# digital-ps.net
KiCad netlist of a schematic drawn in EAGLE
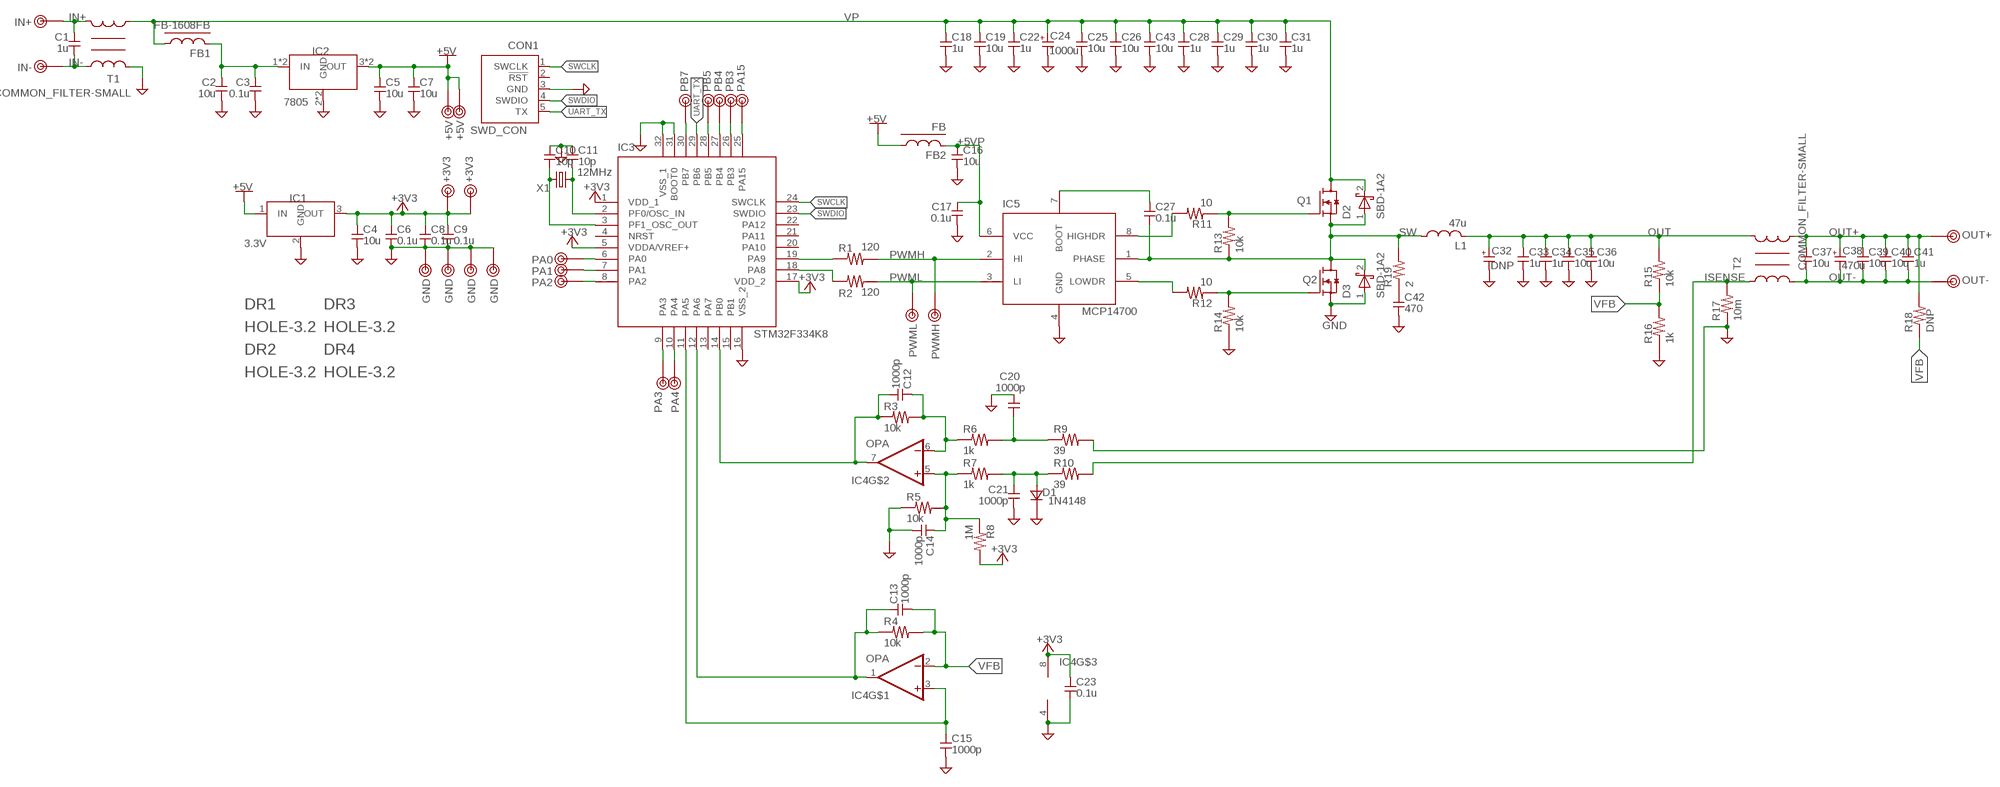
[diagram p0: schematic, sheet 1]

(export (version "E")
  (design (tool "Eeschema 10.0.6"))
  (components
    (comp (ref "C1")
      (value "1u")
      (footprint "eagle-import:2012-2")
      (libsource (lib "eagle-import") (part "C-2012-2"))
    )
    (comp (ref "C2")
      (value "10u")
      (footprint "eagle-import:3216")
      (libsource (lib "eagle-import") (part "C-3216"))
    )
    (comp (ref "C3")
      (value "0.1u")
      (footprint "eagle-import:1608")
      (libsource (lib "eagle-import") (part "C-1608"))
    )
    (comp (ref "C4")
      (value "10u")
      (footprint "eagle-import:2012")
      (libsource (lib "eagle-import") (part "C-2012"))
    )
    (comp (ref "C5")
      (value "10u")
      (footprint "eagle-import:2012")
      (libsource (lib "eagle-import") (part "C-2012"))
    )
    (comp (ref "C6")
      (value "0.1u")
      (footprint "eagle-import:1608")
      (libsource (lib "eagle-import") (part "C-1608"))
    )
    (comp (ref "C7")
      (value "10u")
      (footprint "eagle-import:2012")
      (libsource (lib "eagle-import") (part "C-2012"))
    )
    (comp (ref "C8")
      (value "0.1u")
      (footprint "eagle-import:1608")
      (libsource (lib "eagle-import") (part "C-1608"))
    )
    (comp (ref "C9")
      (value "0.1u")
      (footprint "eagle-import:1608")
      (libsource (lib "eagle-import") (part "C-1608"))
    )
    (comp (ref "C10")
      (value "10p")
      (footprint "eagle-import:1608")
      (libsource (lib "eagle-import") (part "C-1608"))
    )
    (comp (ref "C11")
      (value "10p")
      (footprint "eagle-import:1608")
      (libsource (lib "eagle-import") (part "C-1608"))
    )
    (comp (ref "C12")
      (value "1000p")
      (footprint "eagle-import:1608")
      (libsource (lib "eagle-import") (part "C-1608"))
    )
    (comp (ref "C13")
      (value "1000p")
      (footprint "eagle-import:1608")
      (libsource (lib "eagle-import") (part "C-1608"))
    )
    (comp (ref "C14")
      (value "1000p")
      (footprint "eagle-import:1608")
      (libsource (lib "eagle-import") (part "C-1608"))
    )
    (comp (ref "C15")
      (value "1000p")
      (footprint "eagle-import:1608")
      (libsource (lib "eagle-import") (part "C-1608"))
    )
    (comp (ref "C16")
      (value "10u")
      (footprint "eagle-import:2012")
      (libsource (lib "eagle-import") (part "C-2012"))
    )
    (comp (ref "C17")
      (value "0.1u")
      (footprint "eagle-import:1608")
      (libsource (lib "eagle-import") (part "C-1608"))
    )
    (comp (ref "C18")
      (value "1u")
      (footprint "eagle-import:1608-2")
      (libsource (lib "eagle-import") (part "C-1608-2"))
    )
    (comp (ref "C19")
      (value "10u")
      (footprint "eagle-import:3225-2")
      (libsource (lib "eagle-import") (part "C-3225-2"))
    )
    (comp (ref "C20")
      (value "1000p")
      (footprint "eagle-import:1608")
      (libsource (lib "eagle-import") (part "C-1608"))
    )
    (comp (ref "C21")
      (value "1000p")
      (footprint "eagle-import:1608")
      (libsource (lib "eagle-import") (part "C-1608"))
    )
    (comp (ref "C22")
      (value "1u")
      (footprint "eagle-import:1608-2")
      (libsource (lib "eagle-import") (part "C-1608-2"))
    )
    (comp (ref "C23")
      (value "0.1u")
      (footprint "eagle-import:1608")
      (libsource (lib "eagle-import") (part "C-1608"))
    )
    (comp (ref "C24")
      (value "1000u")
      (footprint "eagle-import:E5-13")
      (libsource (lib "eagle-import") (part "CPOLE5-13"))
    )
    (comp (ref "C25")
      (value "10u")
      (footprint "eagle-import:3225-2")
      (libsource (lib "eagle-import") (part "C-3225-2"))
    )
    (comp (ref "C26")
      (value "10u")
      (footprint "eagle-import:3225-2")
      (libsource (lib "eagle-import") (part "C-3225-2"))
    )
    (comp (ref "C27")
      (value "0.1u")
      (footprint "eagle-import:1608")
      (libsource (lib "eagle-import") (part "C-1608"))
    )
    (comp (ref "C28")
      (value "1u")
      (footprint "eagle-import:1608-2")
      (libsource (lib "eagle-import") (part "C-1608-2"))
    )
    (comp (ref "C29")
      (value "1u")
      (footprint "eagle-import:1608-2")
      (libsource (lib "eagle-import") (part "C-1608-2"))
    )
    (comp (ref "C30")
      (value "1u")
      (footprint "eagle-import:1608-2")
      (libsource (lib "eagle-import") (part "C-1608-2"))
    )
    (comp (ref "C31")
      (value "1u")
      (footprint "eagle-import:1608-2")
      (libsource (lib "eagle-import") (part "C-1608-2"))
    )
    (comp (ref "C32")
      (value "DNP")
      (footprint "eagle-import:E5-13")
      (libsource (lib "eagle-import") (part "CPOLE5-13"))
    )
    (comp (ref "C33")
      (value "1u")
      (footprint "eagle-import:1608-2")
      (libsource (lib "eagle-import") (part "C-1608-2"))
    )
    (comp (ref "C34")
      (value "1u")
      (footprint "eagle-import:1608-2")
      (libsource (lib "eagle-import") (part "C-1608-2"))
    )
    (comp (ref "C35")
      (value "10u")
      (footprint "eagle-import:3225-2")
      (libsource (lib "eagle-import") (part "C-3225-2"))
    )
    (comp (ref "C36")
      (value "10u")
      (footprint "eagle-import:3225-2")
      (libsource (lib "eagle-import") (part "C-3225-2"))
    )
    (comp (ref "C37")
      (value "10u")
      (footprint "eagle-import:3225-2")
      (libsource (lib "eagle-import") (part "C-3225-2"))
    )
    (comp (ref "C38")
      (value "470u")
      (footprint "eagle-import:E5-13")
      (libsource (lib "eagle-import") (part "CPOLE5-13"))
    )
    (comp (ref "C39")
      (value "10u")
      (footprint "eagle-import:3225-2")
      (libsource (lib "eagle-import") (part "C-3225-2"))
    )
    (comp (ref "C40")
      (value "10u")
      (footprint "eagle-import:3225-2")
      (libsource (lib "eagle-import") (part "C-3225-2"))
    )
    (comp (ref "C41")
      (value "1u")
      (footprint "eagle-import:1608-2")
      (libsource (lib "eagle-import") (part "C-1608-2"))
    )
    (comp (ref "C42")
      (value "470")
      (footprint "eagle-import:1608-2")
      (libsource (lib "eagle-import") (part "C-1608-2"))
    )
    (comp (ref "C43")
      (value "10u")
      (footprint "eagle-import:3225-2")
      (libsource (lib "eagle-import") (part "C-3225-2"))
    )
    (comp (ref "CON1")
      (value "SWD_CON")
      (footprint "eagle-import:SWD_CON")
      (libsource (lib "eagle-import") (part "SWD_CON"))
    )
    (comp (ref "D1")
      (value "1N4148")
      (footprint "eagle-import:SOD123")
      (libsource (lib "eagle-import") (part "DIODE-1N4148W"))
    )
    (comp (ref "D2")
      (value "SBD-1A2")
      (footprint "eagle-import:SOD123")
      (libsource (lib "eagle-import") (part "SBD-1A2"))
    )
    (comp (ref "D3")
      (value "SBD-1A2")
      (footprint "eagle-import:SOD123")
      (libsource (lib "eagle-import") (part "SBD-1A2"))
    )
    (comp (ref "DR1")
      (value "HOLE-3.2")
      (footprint "eagle-import:HOLE_3.2")
      (libsource (lib "eagle-import") (part "HOLE-3.2"))
    )
    (comp (ref "DR2")
      (value "HOLE-3.2")
      (footprint "eagle-import:HOLE_3.2")
      (libsource (lib "eagle-import") (part "HOLE-3.2"))
    )
    (comp (ref "DR3")
      (value "HOLE-3.2")
      (footprint "eagle-import:HOLE_3.2")
      (libsource (lib "eagle-import") (part "HOLE-3.2"))
    )
    (comp (ref "DR4")
      (value "HOLE-3.2")
      (footprint "eagle-import:HOLE_3.2")
      (libsource (lib "eagle-import") (part "HOLE-3.2"))
    )
    (comp (ref "FB1")
      (value "FB-1608FB")
      (footprint "eagle-import:1608-FB")
      (libsource (lib "eagle-import") (part "FB-1608FB"))
    )
    (comp (ref "FB2")
      (value "FB")
      (footprint "eagle-import:1608-J")
      (libsource (lib "eagle-import") (part "FB"))
    )
    (comp (ref "IC1")
      (value "3.3V")
      (footprint "eagle-import:P-HSIP3_2.30A")
      (libsource (lib "eagle-import") (part "78X-SOP"))
    )
    (comp (ref "IC2")
      (value "7805")
      (footprint "eagle-import:TO220-SOP-DUAL")
      (libsource (lib "eagle-import") (part "78X-3"))
    )
    (comp (ref "IC3")
      (value "STM32F334K8")
      (footprint "eagle-import:TQFP32-08")
      (libsource (lib "eagle-import") (part "STM32F334K8"))
    )
    (comp (ref "IC4")
      (value "OPA")
      (footprint "eagle-import:SOP8")
      (libsource (lib "eagle-import") (part "OPA-2-SOP"))
    )
    (comp (ref "IC5")
      (value "MCP14700")
      (footprint "eagle-import:SOP8")
      (libsource (lib "eagle-import") (part "MCP14700"))
    )
    (comp (ref "L1")
      (value "47u")
      (footprint "eagle-import:L7-10")
      (libsource (lib "eagle-import") (part "L-7"))
    )
    (comp (ref "Q1")
      (value "EPC2052")
      (footprint "eagle-import:EPC2055")
      (libsource (lib "eagle-import") (part "NMOS-EPC2055"))
    )
    (comp (ref "Q2")
      (value "EPC2052")
      (footprint "eagle-import:EPC2055")
      (libsource (lib "eagle-import") (part "NMOS-EPC2055"))
    )
    (comp (ref "R1")
      (value "120")
      (footprint "eagle-import:1608")
      (libsource (lib "eagle-import") (part "R-1608"))
    )
    (comp (ref "R2")
      (value "120")
      (footprint "eagle-import:1608")
      (libsource (lib "eagle-import") (part "R-1608"))
    )
    (comp (ref "R3")
      (value "10k")
      (footprint "eagle-import:1608")
      (libsource (lib "eagle-import") (part "R-1608"))
    )
    (comp (ref "R4")
      (value "10k")
      (footprint "eagle-import:1608")
      (libsource (lib "eagle-import") (part "R-1608"))
    )
    (comp (ref "R5")
      (value "10k")
      (footprint "eagle-import:1608")
      (libsource (lib "eagle-import") (part "R-1608"))
    )
    (comp (ref "R6")
      (value "1k")
      (footprint "eagle-import:1608")
      (libsource (lib "eagle-import") (part "R-1608"))
    )
    (comp (ref "R7")
      (value "1k")
      (footprint "eagle-import:1608")
      (libsource (lib "eagle-import") (part "R-1608"))
    )
    (comp (ref "R8")
      (value "1M")
      (footprint "eagle-import:1608")
      (libsource (lib "eagle-import") (part "R-1608"))
    )
    (comp (ref "R9")
      (value "39")
      (footprint "eagle-import:1608")
      (libsource (lib "eagle-import") (part "R-1608"))
    )
    (comp (ref "R10")
      (value "39")
      (footprint "eagle-import:1608")
      (libsource (lib "eagle-import") (part "R-1608"))
    )
    (comp (ref "R11")
      (value "10")
      (footprint "eagle-import:2012")
      (libsource (lib "eagle-import") (part "R-2012"))
    )
    (comp (ref "R12")
      (value "10")
      (footprint "eagle-import:2012")
      (libsource (lib "eagle-import") (part "R-2012"))
    )
    (comp (ref "R13")
      (value "10k")
      (footprint "eagle-import:2012")
      (libsource (lib "eagle-import") (part "R-2012"))
    )
    (comp (ref "R14")
      (value "10k")
      (footprint "eagle-import:2012")
      (libsource (lib "eagle-import") (part "R-2012"))
    )
    (comp (ref "R15")
      (value "10k")
      (footprint "eagle-import:1608")
      (libsource (lib "eagle-import") (part "R-1608"))
    )
    (comp (ref "R16")
      (value "1k")
      (footprint "eagle-import:1608")
      (libsource (lib "eagle-import") (part "R-1608"))
    )
    (comp (ref "R17")
      (value "10m")
      (footprint "eagle-import:6432")
      (libsource (lib "eagle-import") (part "R-6432"))
    )
    (comp (ref "R18")
      (value "DNP")
      (footprint "eagle-import:1608")
      (libsource (lib "eagle-import") (part "R-1608"))
    )
    (comp (ref "R19")
      (value "2")
      (footprint "eagle-import:1608-2")
      (libsource (lib "eagle-import") (part "R-1608-2"))
    )
    (comp (ref "T1")
      (value "COMMON_FILTER-SMALL")
      (footprint "eagle-import:COMMON_FILTER__SMALL")
      (libsource (lib "eagle-import") (part "COMMON_FILTER-SMALL"))
    )
    (comp (ref "T2")
      (value "COMMON_FILTER-SMALL")
      (footprint "eagle-import:COMMON_FILTER__SMALL")
      (libsource (lib "eagle-import") (part "COMMON_FILTER-SMALL"))
    )
    (comp (ref "TP1")
      (value "PA0")
      (footprint "eagle-import:TESTPIN")
      (libsource (lib "eagle-import") (part "TESTPIN"))
    )
    (comp (ref "TP2")
      (value "PA1")
      (footprint "eagle-import:TESTPIN")
      (libsource (lib "eagle-import") (part "TESTPIN"))
    )
    (comp (ref "TP3")
      (value "PA2")
      (footprint "eagle-import:TESTPIN")
      (libsource (lib "eagle-import") (part "TESTPIN"))
    )
    (comp (ref "TP4")
      (value "PA3")
      (footprint "eagle-import:TESTPIN")
      (libsource (lib "eagle-import") (part "TESTPIN"))
    )
    (comp (ref "TP5")
      (value "IN+")
      (footprint "eagle-import:TESTPIN-BIG")
      (libsource (lib "eagle-import") (part "TESTPIN-BIG"))
    )
    (comp (ref "TP6")
      (value "IN-")
      (footprint "eagle-import:TESTPIN-BIG")
      (libsource (lib "eagle-import") (part "TESTPIN-BIG"))
    )
    (comp (ref "TP7")
      (value "OUT+")
      (footprint "eagle-import:TESTPIN-BIG")
      (libsource (lib "eagle-import") (part "TESTPIN-BIG"))
    )
    (comp (ref "TP8")
      (value "OUT-")
      (footprint "eagle-import:TESTPIN-BIG")
      (libsource (lib "eagle-import") (part "TESTPIN-BIG"))
    )
    (comp (ref "TP9")
      (value "PA4")
      (footprint "eagle-import:TESTPIN")
      (libsource (lib "eagle-import") (part "TESTPIN"))
    )
    (comp (ref "TP10")
      (value "PB7")
      (footprint "eagle-import:TESTPIN")
      (libsource (lib "eagle-import") (part "TESTPIN"))
    )
    (comp (ref "TP11")
      (value "PB5")
      (footprint "eagle-import:TESTPIN")
      (libsource (lib "eagle-import") (part "TESTPIN"))
    )
    (comp (ref "TP15")
      (value "+3V3")
      (footprint "eagle-import:TESTPIN")
      (libsource (lib "eagle-import") (part "TESTPIN"))
    )
    (comp (ref "TP16")
      (value "+5V")
      (footprint "eagle-import:TESTPIN")
      (libsource (lib "eagle-import") (part "TESTPIN"))
    )
    (comp (ref "TP17")
      (value "GND")
      (footprint "eagle-import:TESTPIN")
      (libsource (lib "eagle-import") (part "TESTPIN"))
    )
    (comp (ref "TP18")
      (value "GND")
      (footprint "eagle-import:TESTPIN")
      (libsource (lib "eagle-import") (part "TESTPIN"))
    )
    (comp (ref "TP19")
      (value "PWML")
      (footprint "eagle-import:TESTPIN")
      (libsource (lib "eagle-import") (part "TESTPIN"))
    )
    (comp (ref "TP20")
      (value "PWMH")
      (footprint "eagle-import:TESTPIN")
      (libsource (lib "eagle-import") (part "TESTPIN"))
    )
    (comp (ref "TP21")
      (value "PA15")
      (footprint "eagle-import:TESTPIN")
      (libsource (lib "eagle-import") (part "TESTPIN"))
    )
    (comp (ref "TP22")
      (value "PB3")
      (footprint "eagle-import:TESTPIN")
      (libsource (lib "eagle-import") (part "TESTPIN"))
    )
    (comp (ref "TP23")
      (value "PB4")
      (footprint "eagle-import:TESTPIN")
      (libsource (lib "eagle-import") (part "TESTPIN"))
    )
    (comp (ref "TP24")
      (value "+3V3")
      (footprint "eagle-import:TESTPIN")
      (libsource (lib "eagle-import") (part "TESTPIN"))
    )
    (comp (ref "TP25")
      (value "GND")
      (footprint "eagle-import:TESTPIN")
      (libsource (lib "eagle-import") (part "TESTPIN"))
    )
    (comp (ref "TP26")
      (value "+5V")
      (footprint "eagle-import:TESTPIN")
      (libsource (lib "eagle-import") (part "TESTPIN"))
    )
    (comp (ref "TP27")
      (value "GND")
      (footprint "eagle-import:TESTPIN")
      (libsource (lib "eagle-import") (part "TESTPIN"))
    )
    (comp (ref "X1")
      (value "12MHz")
      (footprint "eagle-import:HC49_S")
      (libsource (lib "eagle-import") (part "CRYSTALHC49S"))
    )
  )
  (nets
    (net (code "1") (name "+3V3") (class "Default")
      (node (ref "C23") (pin "1") (pinfunction "1_1") (pintype "passive"))
      (node (ref "C4") (pin "1") (pinfunction "1_1") (pintype "passive"))
      (node (ref "C6") (pin "1") (pinfunction "1_1") (pintype "passive"))
      (node (ref "C8") (pin "1") (pinfunction "1_1") (pintype "passive"))
      (node (ref "C9") (pin "1") (pinfunction "1_1") (pintype "passive"))
      (node (ref "IC1") (pin "3") (pinfunction "OUT_3") (pintype "output"))
      (node (ref "IC3") (pin "1") (pinfunction "VDD_1_1") (pintype "power_in"))
      (node (ref "IC3") (pin "17") (pinfunction "VDD_2_17") (pintype "power_in"))
      (node (ref "IC3") (pin "5") (pinfunction "VDDA/VREF+_5") (pintype "power_in"))
      (node (ref "IC4") (pin "8") (pinfunction "V+_8") (pintype "power_in"))
      (node (ref "R8") (pin "2") (pinfunction "2_2") (pintype "passive"))
      (node (ref "TP15") (pin "1") (pinfunction "1_1") (pintype "passive"))
      (node (ref "TP24") (pin "1") (pinfunction "1_1") (pintype "passive"))
    )
    (net (code "2") (name "+5V") (class "Default")
      (node (ref "C5") (pin "1") (pinfunction "1_1") (pintype "passive"))
      (node (ref "C7") (pin "1") (pinfunction "1_1") (pintype "passive"))
      (node (ref "FB2") (pin "1") (pinfunction "1_1") (pintype "passive"))
      (node (ref "IC1") (pin "1") (pinfunction "IN_1") (pintype "input"))
      (node (ref "IC2") (pin "3") (pinfunction "OUT_3") (pintype "output"))
      (node (ref "IC2") (pin "6") (pinfunction "OUT_6") (pintype "output"))
      (node (ref "TP16") (pin "1") (pinfunction "1_1") (pintype "passive"))
      (node (ref "TP26") (pin "1") (pinfunction "1_1") (pintype "passive"))
    )
    (net (code "3") (name "/+5VP") (class "Default")
      (node (ref "C16") (pin "1") (pinfunction "1_1") (pintype "passive"))
      (node (ref "C17") (pin "1") (pinfunction "1_1") (pintype "passive"))
      (node (ref "FB2") (pin "2") (pinfunction "2_2") (pintype "passive"))
      (node (ref "IC5") (pin "6") (pinfunction "VCC_6") (pintype "power_in"))
    )
    (net (code "4") (name "/IN+") (class "Default")
      (node (ref "C1") (pin "1") (pinfunction "1_1") (pintype "passive"))
      (node (ref "T1") (pin "4") (pinfunction "4_4") (pintype "passive"))
      (node (ref "TP5") (pin "1") (pinfunction "1_1") (pintype "passive"))
    )
    (net (code "5") (name "/IN-") (class "Default")
      (node (ref "C1") (pin "2") (pinfunction "2_2") (pintype "passive"))
      (node (ref "T1") (pin "1") (pinfunction "1_1") (pintype "passive"))
      (node (ref "TP6") (pin "1") (pinfunction "1_1") (pintype "passive"))
    )
    (net (code "6") (name "/ISENSE") (class "Default")
      (node (ref "R10") (pin "2") (pinfunction "2_2") (pintype "passive"))
      (node (ref "R17") (pin "2") (pinfunction "2_2") (pintype "passive"))
      (node (ref "T2") (pin "1") (pinfunction "1_1") (pintype "passive"))
    )
    (net (code "7") (name "/OUT") (class "Default")
      (node (ref "C32") (pin "+") (pinfunction "1_+") (pintype "passive"))
      (node (ref "C33") (pin "1") (pinfunction "1_1") (pintype "passive"))
      (node (ref "C34") (pin "1") (pinfunction "1_1") (pintype "passive"))
      (node (ref "C35") (pin "1") (pinfunction "1_1") (pintype "passive"))
      (node (ref "C36") (pin "1") (pinfunction "1_1") (pintype "passive"))
      (node (ref "L1") (pin "2") (pinfunction "2_2") (pintype "passive"))
      (node (ref "R15") (pin "2") (pinfunction "2_2") (pintype "passive"))
      (node (ref "T2") (pin "4") (pinfunction "4_4") (pintype "passive"))
    )
    (net (code "8") (name "/OUT+") (class "Default")
      (node (ref "C37") (pin "1") (pinfunction "1_1") (pintype "passive"))
      (node (ref "C38") (pin "+") (pinfunction "1_+") (pintype "passive"))
      (node (ref "C39") (pin "1") (pinfunction "1_1") (pintype "passive"))
      (node (ref "C40") (pin "1") (pinfunction "1_1") (pintype "passive"))
      (node (ref "C41") (pin "1") (pinfunction "1_1") (pintype "passive"))
      (node (ref "R18") (pin "2") (pinfunction "2_2") (pintype "passive"))
      (node (ref "T2") (pin "3") (pinfunction "3_3") (pintype "passive"))
      (node (ref "TP7") (pin "1") (pinfunction "1_1") (pintype "passive"))
    )
    (net (code "9") (name "/OUT-") (class "Default")
      (node (ref "C37") (pin "2") (pinfunction "2_2") (pintype "passive"))
      (node (ref "C38") (pin "-") (pinfunction "2_-") (pintype "passive"))
      (node (ref "C39") (pin "2") (pinfunction "2_2") (pintype "passive"))
      (node (ref "C40") (pin "2") (pinfunction "2_2") (pintype "passive"))
      (node (ref "C41") (pin "2") (pinfunction "2_2") (pintype "passive"))
      (node (ref "T2") (pin "2") (pinfunction "2_2") (pintype "passive"))
      (node (ref "TP8") (pin "1") (pinfunction "1_1") (pintype "passive"))
    )
    (net (code "10") (name "/PWMH") (class "Default")
      (node (ref "IC5") (pin "2") (pinfunction "HI_2") (pintype "input"))
      (node (ref "R1") (pin "2") (pinfunction "2_2") (pintype "passive"))
      (node (ref "TP20") (pin "1") (pinfunction "1_1") (pintype "passive"))
    )
    (net (code "11") (name "/PWML") (class "Default")
      (node (ref "IC5") (pin "3") (pinfunction "LI_3") (pintype "input"))
      (node (ref "R2") (pin "2") (pinfunction "2_2") (pintype "passive"))
      (node (ref "TP19") (pin "1") (pinfunction "1_1") (pintype "passive"))
    )
    (net (code "12") (name "/SW") (class "Default")
      (node (ref "C27") (pin "2") (pinfunction "2_2") (pintype "passive"))
      (node (ref "D2") (pin "1") (pinfunction "A_1") (pintype "bidirectional"))
      (node (ref "D3") (pin "2") (pinfunction "K_2") (pintype "bidirectional"))
      (node (ref "IC5") (pin "1") (pinfunction "PHASE_1") (pintype "input"))
      (node (ref "L1") (pin "1") (pinfunction "1_1") (pintype "passive"))
      (node (ref "Q1") (pin "2") (pinfunction "S_2") (pintype "passive"))
      (node (ref "Q1") (pin "4") (pinfunction "S_4") (pintype "passive"))
      (node (ref "Q1") (pin "6") (pinfunction "S_6") (pintype "passive"))
      (node (ref "Q2") (pin "3") (pinfunction "D_3") (pintype "passive"))
      (node (ref "Q2") (pin "5") (pinfunction "D_5") (pintype "passive"))
      (node (ref "R13") (pin "1") (pinfunction "1_1") (pintype "passive"))
      (node (ref "R19") (pin "2") (pinfunction "2_2") (pintype "passive"))
    )
    (net (code "13") (name "/VP") (class "Default")
      (node (ref "C18") (pin "1") (pinfunction "1_1") (pintype "passive"))
      (node (ref "C19") (pin "1") (pinfunction "1_1") (pintype "passive"))
      (node (ref "C22") (pin "1") (pinfunction "1_1") (pintype "passive"))
      (node (ref "C24") (pin "+") (pinfunction "1_+") (pintype "passive"))
      (node (ref "C25") (pin "1") (pinfunction "1_1") (pintype "passive"))
      (node (ref "C26") (pin "1") (pinfunction "1_1") (pintype "passive"))
      (node (ref "C28") (pin "1") (pinfunction "1_1") (pintype "passive"))
      (node (ref "C29") (pin "1") (pinfunction "1_1") (pintype "passive"))
      (node (ref "C30") (pin "1") (pinfunction "1_1") (pintype "passive"))
      (node (ref "C31") (pin "1") (pinfunction "1_1") (pintype "passive"))
      (node (ref "C43") (pin "1") (pinfunction "1_1") (pintype "passive"))
      (node (ref "D2") (pin "2") (pinfunction "K_2") (pintype "bidirectional"))
      (node (ref "FB1") (pin "1") (pinfunction "1_1") (pintype "passive"))
      (node (ref "Q1") (pin "3") (pinfunction "D_3") (pintype "passive"))
      (node (ref "Q1") (pin "5") (pinfunction "D_5") (pintype "passive"))
      (node (ref "T1") (pin "3") (pinfunction "3_3") (pintype "passive"))
    )
    (net (code "14") (name "GND") (class "Default")
      (node (ref "C10") (pin "1") (pinfunction "1_1") (pintype "passive"))
      (node (ref "C11") (pin "1") (pinfunction "1_1") (pintype "passive"))
      (node (ref "C14") (pin "2") (pinfunction "2_2") (pintype "passive"))
      (node (ref "C15") (pin "2") (pinfunction "2_2") (pintype "passive"))
      (node (ref "C16") (pin "2") (pinfunction "2_2") (pintype "passive"))
      (node (ref "C17") (pin "2") (pinfunction "2_2") (pintype "passive"))
      (node (ref "C18") (pin "2") (pinfunction "2_2") (pintype "passive"))
      (node (ref "C19") (pin "2") (pinfunction "2_2") (pintype "passive"))
      (node (ref "C2") (pin "2") (pinfunction "2_2") (pintype "passive"))
      (node (ref "C20") (pin "1") (pinfunction "1_1") (pintype "passive"))
      (node (ref "C21") (pin "2") (pinfunction "2_2") (pintype "passive"))
      (node (ref "C22") (pin "2") (pinfunction "2_2") (pintype "passive"))
      (node (ref "C23") (pin "2") (pinfunction "2_2") (pintype "passive"))
      (node (ref "C24") (pin "-") (pinfunction "2_-") (pintype "passive"))
      (node (ref "C25") (pin "2") (pinfunction "2_2") (pintype "passive"))
      (node (ref "C26") (pin "2") (pinfunction "2_2") (pintype "passive"))
      (node (ref "C28") (pin "2") (pinfunction "2_2") (pintype "passive"))
      (node (ref "C29") (pin "2") (pinfunction "2_2") (pintype "passive"))
      (node (ref "C3") (pin "2") (pinfunction "2_2") (pintype "passive"))
      (node (ref "C30") (pin "2") (pinfunction "2_2") (pintype "passive"))
      (node (ref "C31") (pin "2") (pinfunction "2_2") (pintype "passive"))
      (node (ref "C32") (pin "-") (pinfunction "2_-") (pintype "passive"))
      (node (ref "C33") (pin "2") (pinfunction "2_2") (pintype "passive"))
      (node (ref "C34") (pin "2") (pinfunction "2_2") (pintype "passive"))
      (node (ref "C35") (pin "2") (pinfunction "2_2") (pintype "passive"))
      (node (ref "C36") (pin "2") (pinfunction "2_2") (pintype "passive"))
      (node (ref "C4") (pin "2") (pinfunction "2_2") (pintype "passive"))
      (node (ref "C42") (pin "2") (pinfunction "2_2") (pintype "passive"))
      (node (ref "C43") (pin "2") (pinfunction "2_2") (pintype "passive"))
      (node (ref "C5") (pin "2") (pinfunction "2_2") (pintype "passive"))
      (node (ref "C6") (pin "2") (pinfunction "2_2") (pintype "passive"))
      (node (ref "C7") (pin "2") (pinfunction "2_2") (pintype "passive"))
      (node (ref "C8") (pin "2") (pinfunction "2_2") (pintype "passive"))
      (node (ref "C9") (pin "2") (pinfunction "2_2") (pintype "passive"))
      (node (ref "CON1") (pin "3") (pinfunction "GND_3") (pintype "power_in"))
      (node (ref "D1") (pin "2") (pinfunction "K_2") (pintype "passive"))
      (node (ref "D3") (pin "1") (pinfunction "A_1") (pintype "bidirectional"))
      (node (ref "IC1") (pin "2") (pinfunction "GND_2") (pintype "input"))
      (node (ref "IC2") (pin "2") (pinfunction "GND_2") (pintype "input"))
      (node (ref "IC2") (pin "5") (pinfunction "GND_5") (pintype "input"))
      (node (ref "IC3") (pin "16") (pinfunction "VSS_2_16") (pintype "power_in"))
      (node (ref "IC3") (pin "31") (pinfunction "BOOT0_31") (pintype "input"))
      (node (ref "IC3") (pin "32") (pinfunction "VSS_1_32") (pintype "power_in"))
      (node (ref "IC4") (pin "4") (pinfunction "V-_4") (pintype "power_in"))
      (node (ref "IC5") (pin "4") (pinfunction "GND_4") (pintype "power_in"))
      (node (ref "Q2") (pin "2") (pinfunction "S_2") (pintype "passive"))
      (node (ref "Q2") (pin "4") (pinfunction "S_4") (pintype "passive"))
      (node (ref "Q2") (pin "6") (pinfunction "S_6") (pintype "passive"))
      (node (ref "R14") (pin "1") (pinfunction "1_1") (pintype "passive"))
      (node (ref "R16") (pin "1") (pinfunction "1_1") (pintype "passive"))
      (node (ref "R17") (pin "1") (pinfunction "1_1") (pintype "passive"))
      (node (ref "R5") (pin "1") (pinfunction "1_1") (pintype "passive"))
      (node (ref "R9") (pin "2") (pinfunction "2_2") (pintype "passive"))
      (node (ref "T1") (pin "2") (pinfunction "2_2") (pintype "passive"))
      (node (ref "TP17") (pin "1") (pinfunction "1_1") (pintype "passive"))
      (node (ref "TP18") (pin "1") (pinfunction "1_1") (pintype "passive"))
      (node (ref "TP25") (pin "1") (pinfunction "1_1") (pintype "passive"))
      (node (ref "TP27") (pin "1") (pinfunction "1_1") (pintype "passive"))
    )
    (net (code "15") (name "Net-(C2-Pad1)") (class "Default")
      (node (ref "C2") (pin "1") (pinfunction "1_1") (pintype "passive"))
      (node (ref "C3") (pin "1") (pinfunction "1_1") (pintype "passive"))
      (node (ref "FB1") (pin "2") (pinfunction "2_2") (pintype "passive"))
      (node (ref "IC2") (pin "1") (pinfunction "IN_1") (pintype "input"))
      (node (ref "IC2") (pin "4") (pinfunction "IN_4") (pintype "input"))
    )
    (net (code "16") (name "Net-(C20-Pad2)") (class "Default")
      (node (ref "C20") (pin "2") (pinfunction "2_2") (pintype "passive"))
      (node (ref "R6") (pin "2") (pinfunction "2_2") (pintype "passive"))
      (node (ref "R9") (pin "1") (pinfunction "1_1") (pintype "passive"))
    )
    (net (code "17") (name "Net-(C42-Pad1)") (class "Default")
      (node (ref "C42") (pin "1") (pinfunction "1_1") (pintype "passive"))
      (node (ref "R19") (pin "1") (pinfunction "1_1") (pintype "passive"))
    )
    (net (code "18") (name "Net-(D1-A)") (class "Default")
      (node (ref "C21") (pin "1") (pinfunction "1_1") (pintype "passive"))
      (node (ref "D1") (pin "1") (pinfunction "A_1") (pintype "passive"))
      (node (ref "R10") (pin "1") (pinfunction "1_1") (pintype "passive"))
      (node (ref "R7") (pin "2") (pinfunction "2_2") (pintype "passive"))
    )
    (net (code "19") (name "Net-(IC3-PA0)") (class "Default")
      (node (ref "IC3") (pin "6") (pinfunction "PA0_6") (pintype "bidirectional"))
      (node (ref "TP1") (pin "1") (pinfunction "1_1") (pintype "passive"))
    )
    (net (code "20") (name "Net-(IC3-PA1)") (class "Default")
      (node (ref "IC3") (pin "7") (pinfunction "PA1_7") (pintype "bidirectional"))
      (node (ref "TP2") (pin "1") (pinfunction "1_1") (pintype "passive"))
    )
    (net (code "21") (name "Net-(IC3-PA2)") (class "Default")
      (node (ref "IC3") (pin "8") (pinfunction "PA2_8") (pintype "bidirectional"))
      (node (ref "TP3") (pin "1") (pinfunction "1_1") (pintype "passive"))
    )
    (net (code "22") (name "Net-(IC3-PA3)") (class "Default")
      (node (ref "IC3") (pin "9") (pinfunction "PA3_9") (pintype "bidirectional"))
      (node (ref "TP4") (pin "1") (pinfunction "1_1") (pintype "passive"))
    )
    (net (code "23") (name "Net-(IC3-PA4)") (class "Default")
      (node (ref "IC3") (pin "10") (pinfunction "PA4_10") (pintype "bidirectional"))
      (node (ref "TP9") (pin "1") (pinfunction "1_1") (pintype "passive"))
    )
    (net (code "24") (name "Net-(IC3-PA5)") (class "Default")
      (node (ref "C15") (pin "1") (pinfunction "1_1") (pintype "passive"))
      (node (ref "IC3") (pin "11") (pinfunction "PA5_11") (pintype "bidirectional"))
      (node (ref "IC4") (pin "3") (pinfunction "+IN_3") (pintype "input"))
    )
    (net (code "25") (name "Net-(IC3-PA6)") (class "Default")
      (node (ref "C13") (pin "1") (pinfunction "1_1") (pintype "passive"))
      (node (ref "IC3") (pin "12") (pinfunction "PA6_12") (pintype "bidirectional"))
      (node (ref "IC4") (pin "1") (pinfunction "OUT_1") (pintype "output"))
      (node (ref "R4") (pin "1") (pinfunction "1_1") (pintype "passive"))
    )
    (net (code "26") (name "Net-(IC3-PA8)") (class "Default")
      (node (ref "IC3") (pin "18") (pinfunction "PA8_18") (pintype "bidirectional"))
      (node (ref "R2") (pin "1") (pinfunction "1_1") (pintype "passive"))
    )
    (net (code "27") (name "Net-(IC3-PA9)") (class "Default")
      (node (ref "IC3") (pin "19") (pinfunction "PA9_19") (pintype "bidirectional"))
      (node (ref "R1") (pin "1") (pinfunction "1_1") (pintype "passive"))
    )
    (net (code "28") (name "Net-(IC3-PA15)") (class "Default")
      (node (ref "IC3") (pin "25") (pinfunction "PA15_25") (pintype "bidirectional"))
      (node (ref "TP21") (pin "1") (pinfunction "1_1") (pintype "passive"))
    )
    (net (code "29") (name "Net-(IC3-PB0)") (class "Default")
      (node (ref "C12") (pin "2") (pinfunction "2_2") (pintype "passive"))
      (node (ref "IC3") (pin "14") (pinfunction "PB0_14") (pintype "bidirectional"))
      (node (ref "IC4") (pin "7") (pinfunction "OUT_7") (pintype "output"))
      (node (ref "R3") (pin "1") (pinfunction "1_1") (pintype "passive"))
    )
    (net (code "30") (name "Net-(IC3-PB3)") (class "Default")
      (node (ref "IC3") (pin "26") (pinfunction "PB3_26") (pintype "bidirectional"))
      (node (ref "TP22") (pin "1") (pinfunction "1_1") (pintype "passive"))
    )
    (net (code "31") (name "Net-(IC3-PB4)") (class "Default")
      (node (ref "IC3") (pin "27") (pinfunction "PB4_27") (pintype "bidirectional"))
      (node (ref "TP23") (pin "1") (pinfunction "1_1") (pintype "passive"))
    )
    (net (code "32") (name "Net-(IC3-PB5)") (class "Default")
      (node (ref "IC3") (pin "28") (pinfunction "PB5_28") (pintype "bidirectional"))
      (node (ref "TP11") (pin "1") (pinfunction "1_1") (pintype "passive"))
    )
    (net (code "33") (name "Net-(IC3-PB7)") (class "Default")
      (node (ref "IC3") (pin "30") (pinfunction "PB7_30") (pintype "bidirectional"))
      (node (ref "TP10") (pin "1") (pinfunction "1_1") (pintype "passive"))
    )
    (net (code "34") (name "Net-(IC3-PF0{slash}OSC_IN)") (class "Default")
      (node (ref "C11") (pin "2") (pinfunction "2_2") (pintype "passive"))
      (node (ref "IC3") (pin "2") (pinfunction "PF0/OSC_IN_2") (pintype "bidirectional"))
      (node (ref "X1") (pin "1") (pinfunction "1_1") (pintype "passive"))
    )
    (net (code "35") (name "Net-(IC3-PF1_OSC_OUT)") (class "Default")
      (node (ref "C10") (pin "2") (pinfunction "2_2") (pintype "passive"))
      (node (ref "IC3") (pin "3") (pinfunction "PF1_OSC_OUT_3") (pintype "bidirectional"))
      (node (ref "X1") (pin "2") (pinfunction "2_2") (pintype "passive"))
    )
    (net (code "36") (name "Net-(IC4B-+IN)") (class "Default")
      (node (ref "C14") (pin "1") (pinfunction "1_1") (pintype "passive"))
      (node (ref "IC4") (pin "5") (pinfunction "+IN_5") (pintype "input"))
      (node (ref "R5") (pin "2") (pinfunction "2_2") (pintype "passive"))
      (node (ref "R7") (pin "1") (pinfunction "1_1") (pintype "passive"))
      (node (ref "R8") (pin "1") (pinfunction "1_1") (pintype "passive"))
    )
    (net (code "37") (name "Net-(IC4B--IN)") (class "Default")
      (node (ref "C12") (pin "1") (pinfunction "1_1") (pintype "passive"))
      (node (ref "IC4") (pin "6") (pinfunction "-IN_6") (pintype "input"))
      (node (ref "R3") (pin "2") (pinfunction "2_2") (pintype "passive"))
      (node (ref "R6") (pin "1") (pinfunction "1_1") (pintype "passive"))
    )
    (net (code "38") (name "Net-(IC5-BOOT)") (class "Default")
      (node (ref "C27") (pin "1") (pinfunction "1_1") (pintype "passive"))
      (node (ref "IC5") (pin "7") (pinfunction "BOOT_7") (pintype "power_in"))
    )
    (net (code "39") (name "Net-(IC5-HIGHDR)") (class "Default")
      (node (ref "IC5") (pin "8") (pinfunction "HIGHDR_8") (pintype "output"))
      (node (ref "R11") (pin "2") (pinfunction "2_2") (pintype "passive"))
    )
    (net (code "40") (name "Net-(IC5-LOWDR)") (class "Default")
      (node (ref "IC5") (pin "5") (pinfunction "LOWDR_5") (pintype "output"))
      (node (ref "R12") (pin "2") (pinfunction "2_2") (pintype "passive"))
    )
    (net (code "41") (name "Net-(Q1-G)") (class "Default")
      (node (ref "Q1") (pin "1") (pinfunction "G_1") (pintype "passive"))
      (node (ref "R11") (pin "1") (pinfunction "1_1") (pintype "passive"))
      (node (ref "R13") (pin "2") (pinfunction "2_2") (pintype "passive"))
    )
    (net (code "42") (name "Net-(Q2-G)") (class "Default")
      (node (ref "Q2") (pin "1") (pinfunction "G_1") (pintype "passive"))
      (node (ref "R12") (pin "1") (pinfunction "1_1") (pintype "passive"))
      (node (ref "R14") (pin "2") (pinfunction "2_2") (pintype "passive"))
    )
    (net (code "43") (name "SWCLK") (class "Default")
      (node (ref "CON1") (pin "1") (pinfunction "SWCLK_1") (pintype "bidirectional"))
      (node (ref "IC3") (pin "24") (pinfunction "SWCLK_24") (pintype "bidirectional"))
    )
    (net (code "44") (name "SWDIO") (class "Default")
      (node (ref "CON1") (pin "4") (pinfunction "SWDIO_4") (pintype "bidirectional"))
      (node (ref "IC3") (pin "23") (pinfunction "SWDIO_23") (pintype "bidirectional"))
    )
    (net (code "45") (name "UART_TX") (class "Default")
      (node (ref "CON1") (pin "5") (pinfunction "TX_5") (pintype "bidirectional"))
      (node (ref "IC3") (pin "29") (pinfunction "PB6_29") (pintype "bidirectional"))
    )
    (net (code "46") (name "VFB") (class "Default")
      (node (ref "C13") (pin "2") (pinfunction "2_2") (pintype "passive"))
      (node (ref "IC4") (pin "2") (pinfunction "-IN_2") (pintype "input"))
      (node (ref "R15") (pin "1") (pinfunction "1_1") (pintype "passive"))
      (node (ref "R16") (pin "2") (pinfunction "2_2") (pintype "passive"))
      (node (ref "R18") (pin "1") (pinfunction "1_1") (pintype "passive"))
      (node (ref "R4") (pin "2") (pinfunction "2_2") (pintype "passive"))
    )
    (net (code "47") (name "unconnected-(CON1-~{RST}-Pad2)") (class "Default")
      (node (ref "CON1") (pin "2") (pinfunction "~{RST}_2") (pintype "bidirectional"))
    )
    (net (code "48") (name "unconnected-(IC3-NRST-Pad4)") (class "Default")
      (node (ref "IC3") (pin "4") (pinfunction "NRST_4") (pintype "bidirectional"))
    )
    (net (code "49") (name "unconnected-(IC3-PA7-Pad13)") (class "Default")
      (node (ref "IC3") (pin "13") (pinfunction "PA7_13") (pintype "bidirectional"))
    )
    (net (code "50") (name "unconnected-(IC3-PA10-Pad20)") (class "Default")
      (node (ref "IC3") (pin "20") (pinfunction "PA10_20") (pintype "bidirectional"))
    )
    (net (code "51") (name "unconnected-(IC3-PA11-Pad21)") (class "Default")
      (node (ref "IC3") (pin "21") (pinfunction "PA11_21") (pintype "bidirectional"))
    )
    (net (code "52") (name "unconnected-(IC3-PA12-Pad22)") (class "Default")
      (node (ref "IC3") (pin "22") (pinfunction "PA12_22") (pintype "bidirectional"))
    )
    (net (code "53") (name "unconnected-(IC3-PB1-Pad15)") (class "Default")
      (node (ref "IC3") (pin "15") (pinfunction "PB1_15") (pintype "bidirectional"))
    )
  )
)
